# Memory.net
KiCad netlist of a schematic drawn in Altium Designer
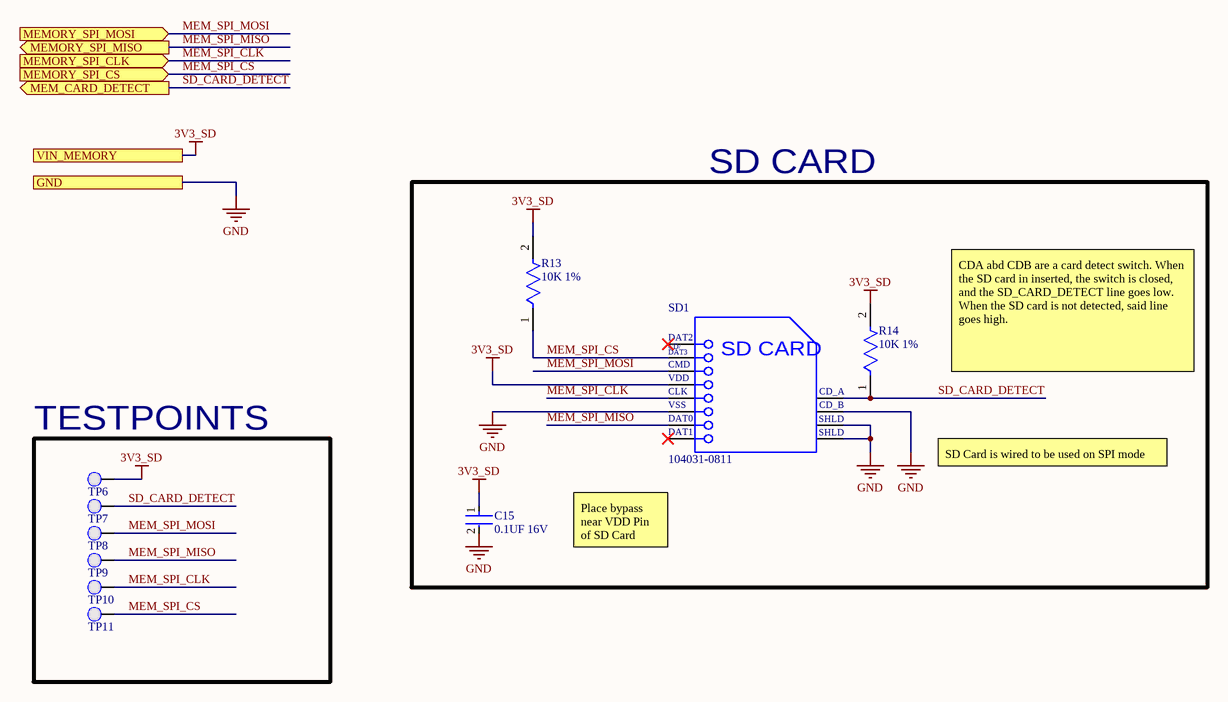
[diagram p0: Memory.SchDoc]

(export (version "E")
  (design (tool "Eeschema 10.0.6"))
  (components
    (comp (ref "C15")
      (value "0.1UF 16V")
      (footprint "FP-CC0402-MFG")
      (description "CC0402 100 nF X7R 10.00% 25 V")
      (fields
        (field (name "MANUFACTURER PART NUMBER") "CC0402KPX7R8BB104")
        (field (name "MANUFACTURER") "YAGEO")
      )
      (libsource (lib "Altium Content Vault") (part "11868f565c42a9108669ba33697ecf6"))
    )
    (comp (ref "R13")
      (value "10K 1%")
      (footprint "FP-RNCP0603-IPC_A")
      (description "10kΩ ±1% 0.125W 0603 High Power Anti-Sulfur Thin Film Chip Resistor")
      (fields (field (name "TOLERANCE") "1%"))
      (libsource (lib "Altium Content Vault") (part "1029c3af85768c4190bb7ad29bc67b5"))
    )
    (comp (ref "R14")
      (value "10K 1%")
      (footprint "FP-RNCP0603-IPC_A")
      (description "10kΩ ±1% 0.125W 0603 High Power Anti-Sulfur Thin Film Chip Resistor")
      (fields (field (name "TOLERANCE") "1%"))
      (libsource (lib "Altium Content Vault") (part "1029c3af85768c4190bb7ad29bc67b5"))
    )
    (comp (ref "SD1")
      (value "104031-0811")
      (footprint "MOLX-104031-0811_V")
      (description "Micro SD Card, RA, -25 to 85 degC, 8-Pin SMD, RoHS, Tape and Reel")
      (fields (field (name "MANUFACTURER") "Molex"))
      (libsource (lib "Altium Content Vault") (part "CN-SD-8-2SW-2S"))
    )
    (comp (ref "TP6")
      (value "Test Point 0.1\"")
      (footprint "Test Point 0.1\"-Footprint-1")
      (libsource (lib "University of Pennsylvania (ESE Labs)") (part "Test Point 0.1{dblquote}-Symbol-1"))
    )
    (comp (ref "TP7")
      (value "Test Point 0.1\"")
      (footprint "Test Point 0.1\"-Footprint-1")
      (libsource (lib "University of Pennsylvania (ESE Labs)") (part "Test Point 0.1{dblquote}-Symbol-1"))
    )
    (comp (ref "TP8")
      (value "Test Point 0.1\"")
      (footprint "Test Point 0.1\"-Footprint-1")
      (libsource (lib "University of Pennsylvania (ESE Labs)") (part "Test Point 0.1{dblquote}-Symbol-1"))
    )
    (comp (ref "TP9")
      (value "Test Point 0.1\"")
      (footprint "Test Point 0.1\"-Footprint-1")
      (libsource (lib "University of Pennsylvania (ESE Labs)") (part "Test Point 0.1{dblquote}-Symbol-1"))
    )
    (comp (ref "TP10")
      (value "Test Point 0.1\"")
      (footprint "Test Point 0.1\"-Footprint-1")
      (libsource (lib "University of Pennsylvania (ESE Labs)") (part "Test Point 0.1{dblquote}-Symbol-1"))
    )
    (comp (ref "TP11")
      (value "Test Point 0.1\"")
      (footprint "Test Point 0.1\"-Footprint-1")
      (libsource (lib "University of Pennsylvania (ESE Labs)") (part "Test Point 0.1{dblquote}-Symbol-1"))
    )
  )
  (nets
    (net (code "1") (name "/MEM_SPI_CLK") (class "Default")
      (node (ref "SD1") (pin "5") (pinfunction "CLK_5") (pintype "passive"))
      (node (ref "TP10") (pin "1") (pinfunction "PAD_1") (pintype "passive"))
    )
    (net (code "2") (name "/MEM_SPI_CS") (class "Default")
      (node (ref "R13") (pin "1") (pinfunction "1_1") (pintype "passive"))
      (node (ref "SD1") (pin "2") (pinfunction "CMD_2") (pintype "passive"))
      (node (ref "TP11") (pin "1") (pinfunction "PAD_1") (pintype "passive"))
    )
    (net (code "3") (name "/MEM_SPI_MISO") (class "Default")
      (node (ref "SD1") (pin "7") (pinfunction "DAT0_7") (pintype "passive"))
      (node (ref "TP9") (pin "1") (pinfunction "PAD_1") (pintype "passive"))
    )
    (net (code "4") (name "/MEM_SPI_MOSI") (class "Default")
      (node (ref "SD1") (pin "3") (pinfunction "VSS1_3") (pintype "passive"))
      (node (ref "TP8") (pin "1") (pinfunction "PAD_1") (pintype "passive"))
    )
    (net (code "5") (name "/SD_CARD_DETECT") (class "Default")
      (node (ref "R14") (pin "1") (pinfunction "1_1") (pintype "passive"))
      (node (ref "SD1") (pin "9") (pinfunction "CD_A_9") (pintype "passive"))
      (node (ref "TP7") (pin "1") (pinfunction "PAD_1") (pintype "passive"))
    )
    (net (code "6") (name "3V3_SD") (class "Default")
      (node (ref "C15") (pin "1") (pinfunction "1_1") (pintype "passive"))
      (node (ref "R13") (pin "2") (pinfunction "2_2") (pintype "passive"))
      (node (ref "R14") (pin "2") (pinfunction "2_2") (pintype "passive"))
      (node (ref "SD1") (pin "4") (pinfunction "VDD_4") (pintype "passive"))
      (node (ref "TP6") (pin "1") (pinfunction "PAD_1") (pintype "passive"))
    )
    (net (code "7") (name "GND") (class "Default")
      (node (ref "C15") (pin "2") (pinfunction "2_2") (pintype "passive"))
      (node (ref "SD1") (pin "10") (pinfunction "CD_B_10") (pintype "passive"))
      (node (ref "SD1") (pin "11") (pinfunction "SHLD1_11") (pintype "passive"))
      (node (ref "SD1") (pin "12") (pinfunction "SHLD2_12") (pintype "passive"))
      (node (ref "SD1") (pin "6") (pinfunction "VSS2_6") (pintype "passive"))
    )
    (net (code "8") (name "unconnected-(SD1-CD{slash}DAT3-Pad1)") (class "Default")
      (node (ref "SD1") (pin "1") (pinfunction "CD/DAT3_1") (pintype "passive+no_connect"))
    )
    (net (code "9") (name "unconnected-(SD1-DAT1-Pad8)") (class "Default")
      (node (ref "SD1") (pin "8") (pinfunction "DAT1_8") (pintype "passive+no_connect"))
    )
  )
)
